# Sensor.net
KiCad netlist of a schematic drawn in Altium Designer
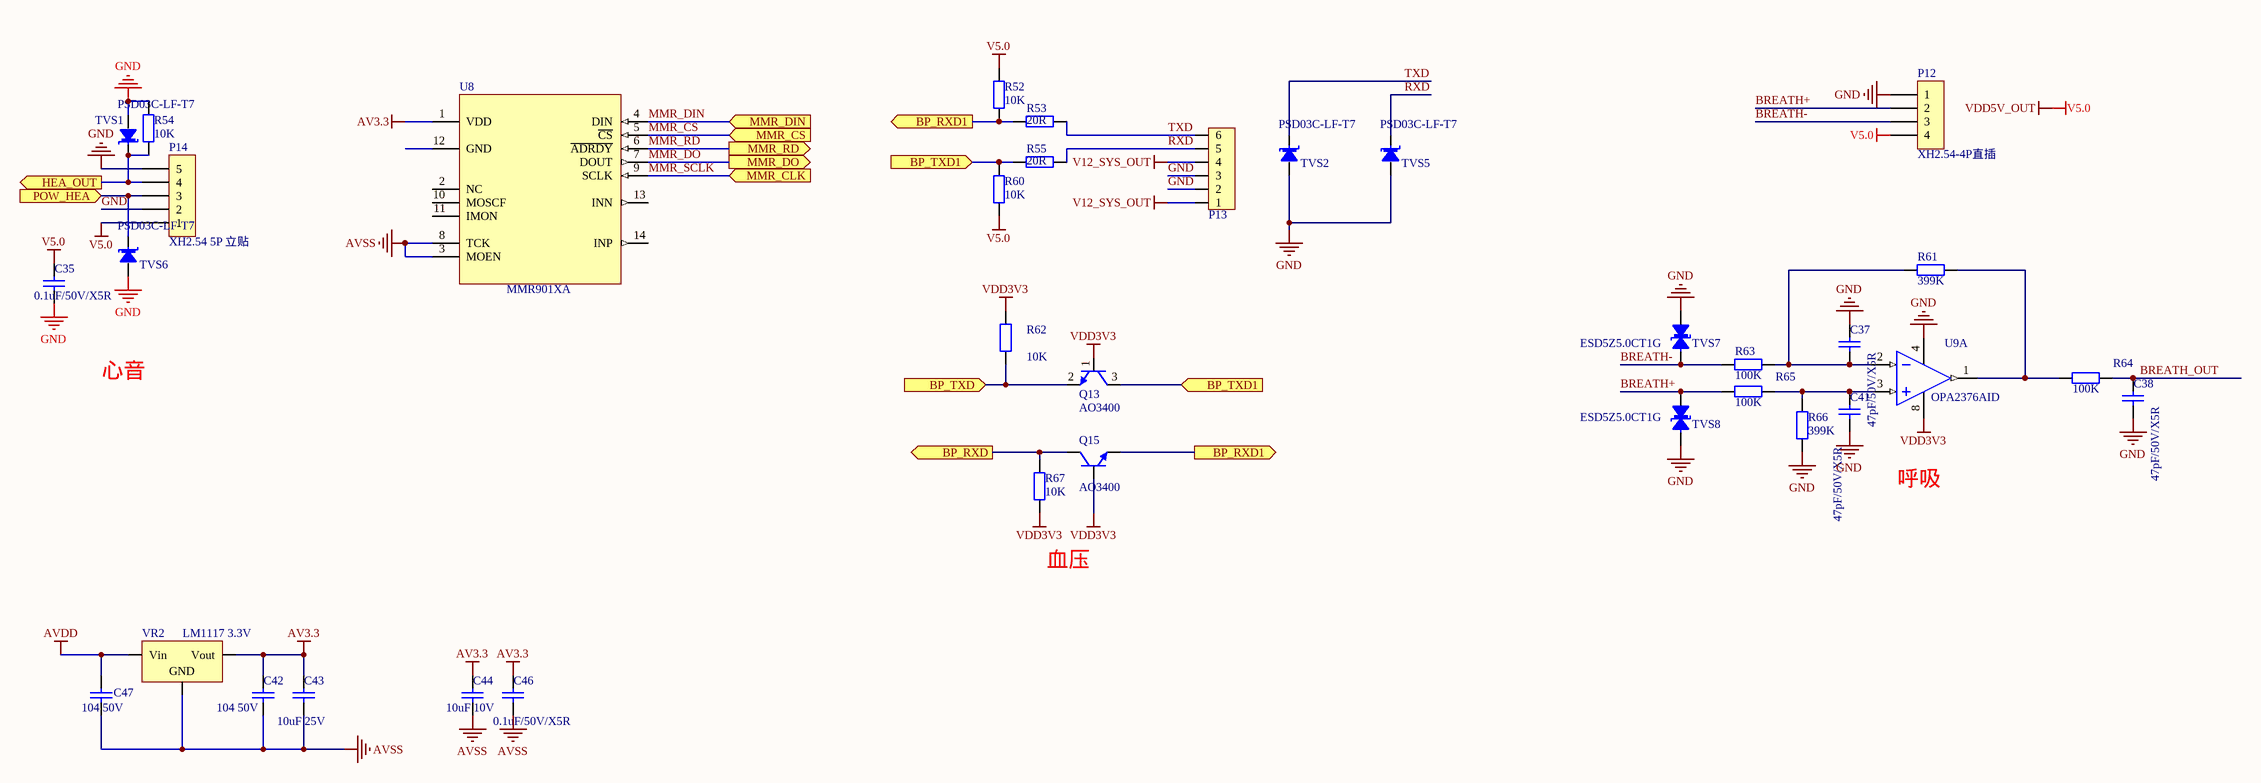
[diagram p0: Sensor.SchDoc]

(export (version "E")
  (design (tool "Eeschema 10.0.6"))
  (components
    (comp (ref "C35")
      (value "0.1uF/50V/X5R")
      (footprint "SMD-0603C")
      (description "贴片电容 20%")
      (libsource (lib "XiaoyI") (part "CAP4"))
    )
    (comp (ref "C37")
      (value "47pF/50V/X5R")
      (footprint "SMD-0603C")
      (description "贴片电容 10%")
      (libsource (lib "XiaoyI") (part "CAP4"))
    )
    (comp (ref "C38")
      (value "47pF/50V/X5R")
      (footprint "SMD-0603C")
      (description "贴片电容 10%")
      (libsource (lib "XiaoyI") (part "CAP4"))
    )
    (comp (ref "C41")
      (value "47pF/50V/X5R")
      (footprint "SMD-0603C")
      (description "贴片电容 10%")
      (libsource (lib "XiaoyI") (part "CAP4"))
    )
    (comp (ref "C42")
      (value "104 50V")
      (footprint "SMD-0603C")
      (description "贴片电容 10%")
      (libsource (lib "XiaoyI") (part "CAP4"))
    )
    (comp (ref "C43")
      (value "10uF 25V")
      (footprint "SMD-0603C")
      (description "贴片电容 20%")
      (libsource (lib "XiaoyI") (part "CAP4"))
    )
    (comp (ref "C44")
      (value "10uF 10V")
      (footprint "SMD-0603C")
      (description "贴片电容 20%")
      (libsource (lib "XiaoyI") (part "CAP4"))
    )
    (comp (ref "C46")
      (value "0.1uF/50V/X5R")
      (footprint "SMD-0603C")
      (description "贴片电容 10%")
      (libsource (lib "XiaoyI") (part "CAP4"))
    )
    (comp (ref "C47")
      (value "104 50V")
      (footprint "SMD-0603C")
      (description "贴片电容 10%")
      (libsource (lib "XiaoyI") (part "CAP4"))
    )
    (comp (ref "P12") (value "XH2.54-4P直插") (footprint "4X2.54MMw") (libsource (lib "ABB") (part "SIP-4")))
    (comp (ref "P13")
      (value "XH2.54 6P 立贴")
      (footprint "6X2.54MMW")
      (description "血压计接口")
      (libsource (lib "ABB") (part "SIP-6"))
    )
    (comp (ref "P14")
      (value "XH2.54 5P 立贴")
      (footprint "5X2.54MMW")
      (description "心音传感器接口")
      (libsource (lib "ABB") (part "SIP-5"))
    )
    (comp (ref "Q13")
      (value "AO3400")
      (footprint "SOT-23")
      (description "NPN")
      (libsource (lib "") (part "NPN-1_1"))
    )
    (comp (ref "Q15")
      (value "AO3400")
      (footprint "SOT-23")
      (description "NPN")
      (libsource (lib "XiaoyI") (part "NPN-1"))
    )
    (comp (ref "R52")
      (value "10K")
      (footprint "SMD-0603")
      (description "贴片电阻 1%")
      (libsource (lib "") (part "RES2_2"))
    )
    (comp (ref "R53")
      (value "20R")
      (footprint "SMD-0603")
      (description "贴片电阻 1%")
      (libsource (lib "") (part "RES2_3"))
    )
    (comp (ref "R54")
      (value "10K")
      (footprint "SMD-0603")
      (description "贴片电阻 1%")
      (libsource (lib "") (part "RES2_2"))
    )
    (comp (ref "R55")
      (value "20R")
      (footprint "SMD-0603")
      (description "贴片电阻 1%")
      (libsource (lib "") (part "RES2_3"))
    )
    (comp (ref "R60")
      (value "10K")
      (footprint "SMD-0603")
      (description "贴片电阻 1%")
      (libsource (lib "") (part "RES2_2"))
    )
    (comp (ref "R61")
      (value "399K")
      (footprint "SMD-0603")
      (description "贴片电阻 1%")
      (libsource (lib "") (part "RES2_1"))
    )
    (comp (ref "R62")
      (value "10K")
      (footprint "SMD-0603")
      (description "贴片电阻 1%")
      (libsource (lib "XiaoyI") (part "RES2"))
    )
    (comp (ref "R63")
      (value "100K")
      (footprint "SMD-0603")
      (description "贴片电阻 1%")
      (libsource (lib "") (part "RES2_1"))
    )
    (comp (ref "R64")
      (value "100K")
      (footprint "SMD-0603")
      (description "贴片电阻 1%")
      (libsource (lib "") (part "RES2_1"))
    )
    (comp (ref "R65")
      (value "100K")
      (footprint "SMD-0603")
      (description "贴片电阻 1%")
      (libsource (lib "") (part "RES2_1"))
    )
    (comp (ref "R66")
      (value "399K")
      (footprint "SMD-0603")
      (description "贴片电阻 1%")
      (libsource (lib "XiaoyI") (part "RES2"))
    )
    (comp (ref "R67")
      (value "10K")
      (footprint "SMD-0603")
      (description "贴片电阻 1%")
      (libsource (lib "XiaoyI") (part "RES2"))
    )
    (comp (ref "TVS1")
      (value "PSD03C-LF-T7")
      (footprint "SOD-323")
      (description "单向TVS")
      (libsource (lib "") (part "TVS-S_1"))
    )
    (comp (ref "TVS2")
      (value "PSD03C-LF-T7")
      (footprint "SOD-323")
      (description "单向TVS")
      (libsource (lib "XiaoyI") (part "TVS-S"))
    )
    (comp (ref "TVS5")
      (value "PSD03C-LF-T7")
      (footprint "SOD-323")
      (description "单向TVS")
      (libsource (lib "XiaoyI") (part "TVS-S"))
    )
    (comp (ref "TVS6")
      (value "PSD03C-LF-T7")
      (footprint "SOD-323")
      (description "单向TVS")
      (libsource (lib "XiaoyI") (part "TVS-S"))
    )
    (comp (ref "TVS7")
      (value "ESD5Z5.0CT1G")
      (footprint "SOD-523")
      (description "ESD二极管")
      (libsource (lib "XiaoyI") (part "TVS-1"))
    )
    (comp (ref "TVS8")
      (value "ESD5Z5.0CT1G")
      (footprint "SOD-523")
      (description "ESD二极管")
      (libsource (lib "XiaoyI") (part "TVS-1"))
    )
    (comp (ref "U8")
      (value "MMR901XA")
      (footprint "MMR901XA")
      (description "压力传感器")
      (libsource (lib "XiaoyI") (part "MMR901"))
    )
    (comp (ref "U9")
      (value "OPA2376AID")
      (footprint "SOIC-8")
      (description "运放")
      (libsource (lib "XiaoyI") (part "LM358"))
    )
    (comp (ref "VR2")
      (value "LM1117 3.3V")
      (footprint "SOT223")
      (description "三端稳压器")
      (libsource (lib "XiaoyI") (part "LM1117"))
    )
  )
  (nets
    (net (code "1") (name "/BP_RXD") (class "Default")
      (node (ref "Q15") (pin "3") (pinfunction "C_3") (pintype "passive"))
      (node (ref "R67") (pin "2") (pinfunction "2_2") (pintype "passive"))
    )
    (net (code "2") (name "/BP_RXD1") (class "Default")
      (node (ref "Q15") (pin "2") (pinfunction "E_2") (pintype "passive"))
      (node (ref "R52") (pin "2") (pinfunction "2_2") (pintype "passive"))
      (node (ref "R53") (pin "2") (pinfunction "2_2") (pintype "passive"))
    )
    (net (code "3") (name "/BP_TXD") (class "Default")
      (node (ref "Q13") (pin "2") (pinfunction "E_2") (pintype "passive"))
      (node (ref "R62") (pin "1") (pinfunction "1_1") (pintype "passive"))
    )
    (net (code "4") (name "/BP_TXD1") (class "Default")
      (node (ref "Q13") (pin "3") (pinfunction "C_3") (pintype "passive"))
      (node (ref "R55") (pin "2") (pinfunction "2_2") (pintype "passive"))
      (node (ref "R60") (pin "1") (pinfunction "1_1") (pintype "passive"))
    )
    (net (code "5") (name "/BREATH+") (class "Default")
      (node (ref "P12") (pin "2") (pinfunction "2_2") (pintype "passive"))
      (node (ref "R65") (pin "1") (pinfunction "1_1") (pintype "passive"))
      (node (ref "TVS8") (pin "1") (pinfunction "A_1") (pintype "passive"))
    )
    (net (code "6") (name "/BREATH-") (class "Default")
      (node (ref "P12") (pin "3") (pinfunction "3_3") (pintype "passive"))
      (node (ref "R63") (pin "1") (pinfunction "1_1") (pintype "passive"))
      (node (ref "TVS7") (pin "2") (pinfunction "B_2") (pintype "passive"))
    )
    (net (code "7") (name "/BREATH_OUT") (class "Default")
      (node (ref "C38") (pin "2") (pinfunction "2_2") (pintype "passive"))
      (node (ref "R64") (pin "2") (pinfunction "2_2") (pintype "passive"))
    )
    (net (code "8") (name "/HEA_OUT") (class "Default")
      (node (ref "P14") (pin "4") (pinfunction "4_4") (pintype "passive"))
      (node (ref "R54") (pin "2") (pinfunction "2_2") (pintype "passive"))
      (node (ref "TVS1") (pin "2") (pinfunction "B_2") (pintype "passive"))
    )
    (net (code "9") (name "/MMR_CS") (class "Default")
      (node (ref "U8") (pin "5") (pinfunction "~{CS}_5") (pintype "input"))
    )
    (net (code "10") (name "/MMR_DIN") (class "Default")
      (node (ref "U8") (pin "4") (pinfunction "DIN_4") (pintype "input"))
    )
    (net (code "11") (name "/MMR_DO") (class "Default")
      (node (ref "U8") (pin "7") (pinfunction "DOUT_7") (pintype "output"))
    )
    (net (code "12") (name "/MMR_RD") (class "Default")
      (node (ref "U8") (pin "6") (pinfunction "~{ADRDY}_6") (pintype "input"))
    )
    (net (code "13") (name "/MMR_SCLK") (class "Default")
      (node (ref "U8") (pin "9") (pinfunction "SCLK_9") (pintype "input"))
    )
    (net (code "14") (name "/POW_HEA") (class "Default")
      (node (ref "P14") (pin "3") (pinfunction "3_3") (pintype "passive"))
      (node (ref "TVS6") (pin "2") (pinfunction "B_2") (pintype "passive"))
    )
    (net (code "15") (name "/RXD") (class "Default")
      (node (ref "P13") (pin "5") (pinfunction "5_5") (pintype "passive"))
      (node (ref "R55") (pin "1") (pinfunction "1_1") (pintype "passive"))
      (node (ref "TVS5") (pin "2") (pinfunction "B_2") (pintype "passive"))
    )
    (net (code "16") (name "/TXD") (class "Default")
      (node (ref "P13") (pin "6") (pinfunction "6_6") (pintype "passive"))
      (node (ref "R53") (pin "1") (pinfunction "1_1") (pintype "passive"))
      (node (ref "TVS2") (pin "2") (pinfunction "B_2") (pintype "passive"))
    )
    (net (code "17") (name "AV3.3") (class "Default")
      (node (ref "C42") (pin "2") (pinfunction "2_2") (pintype "passive"))
      (node (ref "C43") (pin "2") (pinfunction "2_2") (pintype "passive"))
      (node (ref "C44") (pin "2") (pinfunction "2_2") (pintype "passive"))
      (node (ref "C46") (pin "2") (pinfunction "2_2") (pintype "passive"))
      (node (ref "U8") (pin "1") (pinfunction "VDD_1") (pintype "power_in"))
      (node (ref "VR2") (pin "2") (pinfunction "Vout_2") (pintype "passive"))
    )
    (net (code "18") (name "AVDD") (class "Default")
      (node (ref "C47") (pin "2") (pinfunction "2_2") (pintype "passive"))
      (node (ref "VR2") (pin "3") (pinfunction "Vin_3") (pintype "passive"))
    )
    (net (code "19") (name "AVSS") (class "Default")
      (node (ref "C42") (pin "1") (pinfunction "1_1") (pintype "passive"))
      (node (ref "C43") (pin "1") (pinfunction "1_1") (pintype "passive"))
      (node (ref "C44") (pin "1") (pinfunction "1_1") (pintype "passive"))
      (node (ref "C46") (pin "1") (pinfunction "1_1") (pintype "passive"))
      (node (ref "C47") (pin "1") (pinfunction "1_1") (pintype "passive"))
      (node (ref "U8") (pin "3") (pinfunction "MOEN_3") (pintype "passive"))
      (node (ref "U8") (pin "8") (pinfunction "TCK_8") (pintype "passive"))
      (node (ref "VR2") (pin "1") (pinfunction "GND_1") (pintype "passive"))
    )
    (net (code "20") (name "GND") (class "Default")
      (node (ref "C35") (pin "1") (pinfunction "1_1") (pintype "passive"))
      (node (ref "C37") (pin "2") (pinfunction "2_2") (pintype "passive"))
      (node (ref "C38") (pin "1") (pinfunction "1_1") (pintype "passive"))
      (node (ref "C41") (pin "1") (pinfunction "1_1") (pintype "passive"))
      (node (ref "P12") (pin "1") (pinfunction "1_1") (pintype "passive"))
      (node (ref "P13") (pin "2") (pinfunction "2_2") (pintype "passive"))
      (node (ref "P13") (pin "3") (pinfunction "3_3") (pintype "passive"))
      (node (ref "P14") (pin "2") (pinfunction "2_2") (pintype "passive"))
      (node (ref "P14") (pin "5") (pinfunction "5_5") (pintype "passive"))
      (node (ref "R54") (pin "1") (pinfunction "1_1") (pintype "passive"))
      (node (ref "R66") (pin "1") (pinfunction "1_1") (pintype "passive"))
      (node (ref "TVS1") (pin "1") (pinfunction "A_1") (pintype "passive"))
      (node (ref "TVS2") (pin "1") (pinfunction "A_1") (pintype "passive"))
      (node (ref "TVS5") (pin "1") (pinfunction "A_1") (pintype "passive"))
      (node (ref "TVS6") (pin "1") (pinfunction "A_1") (pintype "passive"))
      (node (ref "TVS7") (pin "1") (pinfunction "A_1") (pintype "passive"))
      (node (ref "TVS8") (pin "2") (pinfunction "B_2") (pintype "passive"))
      (node (ref "U9") (pin "4") (pinfunction "V-_4") (pintype "power_in"))
    )
    (net (code "21") (name "Net-(U9A-IN1+)") (class "Default")
      (node (ref "C41") (pin "2") (pinfunction "2_2") (pintype "passive"))
      (node (ref "R65") (pin "2") (pinfunction "2_2") (pintype "passive"))
      (node (ref "R66") (pin "2") (pinfunction "2_2") (pintype "passive"))
      (node (ref "U9") (pin "3") (pinfunction "IN1+_3") (pintype "input"))
    )
    (net (code "22") (name "Net-(U9A-IN1-)") (class "Default")
      (node (ref "C37") (pin "1") (pinfunction "1_1") (pintype "passive"))
      (node (ref "R61") (pin "1") (pinfunction "1_1") (pintype "passive"))
      (node (ref "R63") (pin "2") (pinfunction "2_2") (pintype "passive"))
      (node (ref "U9") (pin "2") (pinfunction "IN1-_2") (pintype "input"))
    )
    (net (code "23") (name "Net-(U9A-OUT1)") (class "Default")
      (node (ref "R61") (pin "2") (pinfunction "2_2") (pintype "passive"))
      (node (ref "R64") (pin "1") (pinfunction "1_1") (pintype "passive"))
      (node (ref "U9") (pin "1") (pinfunction "OUT1_1") (pintype "output"))
    )
    (net (code "24") (name "V5.0") (class "Default")
      (node (ref "C35") (pin "2") (pinfunction "2_2") (pintype "passive"))
      (node (ref "P12") (pin "4") (pinfunction "4_4") (pintype "passive"))
      (node (ref "P14") (pin "1") (pinfunction "1_1") (pintype "passive"))
      (node (ref "R52") (pin "1") (pinfunction "1_1") (pintype "passive"))
      (node (ref "R60") (pin "2") (pinfunction "2_2") (pintype "passive"))
    )
    (net (code "25") (name "V12_SYS_OUT") (class "Default")
      (node (ref "P13") (pin "1") (pinfunction "1_1") (pintype "passive"))
      (node (ref "P13") (pin "4") (pinfunction "4_4") (pintype "passive"))
    )
    (net (code "26") (name "VDD3V3") (class "Default")
      (node (ref "Q13") (pin "1") (pinfunction "B_1") (pintype "passive"))
      (node (ref "Q15") (pin "1") (pinfunction "B_1") (pintype "passive"))
      (node (ref "R62") (pin "2") (pinfunction "2_2") (pintype "passive"))
      (node (ref "R67") (pin "1") (pinfunction "1_1") (pintype "passive"))
      (node (ref "U9") (pin "8") (pinfunction "V+_8") (pintype "power_in"))
    )
    (net (code "27") (name "unconnected-(U8-GND-Pad12)") (class "Default")
      (node (ref "U8") (pin "12") (pinfunction "GND_12") (pintype "power_in"))
    )
    (net (code "28") (name "unconnected-(U8-IMON-Pad11)") (class "Default")
      (node (ref "U8") (pin "11") (pinfunction "IMON_11") (pintype "passive"))
    )
    (net (code "29") (name "unconnected-(U8-INN-Pad13)") (class "Default")
      (node (ref "U8") (pin "13") (pinfunction "INN_13") (pintype "output"))
    )
    (net (code "30") (name "unconnected-(U8-INP-Pad14)") (class "Default")
      (node (ref "U8") (pin "14") (pinfunction "INP_14") (pintype "output"))
    )
    (net (code "31") (name "unconnected-(U8-MOSCF-Pad10)") (class "Default")
      (node (ref "U8") (pin "10") (pinfunction "MOSCF_10") (pintype "passive"))
    )
    (net (code "32") (name "unconnected-(U8-NC-Pad2)") (class "Default")
      (node (ref "U8") (pin "2") (pinfunction "NC_2") (pintype "passive"))
    )
  )
)
